# Display.net
KiCad netlist of a schematic drawn in Altium Designer
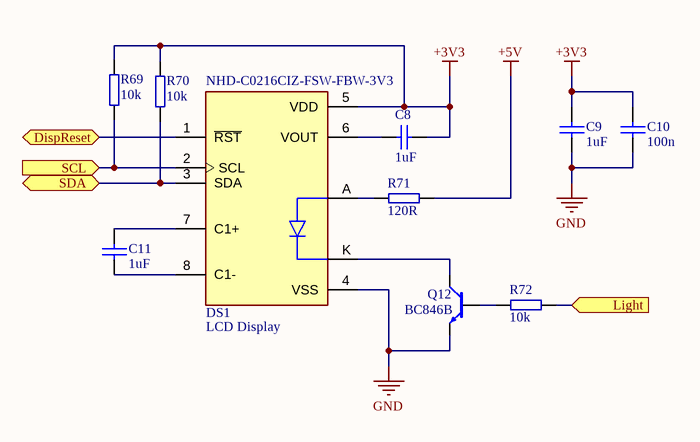
[diagram p0: Display.SchDoc]

(export (version "E")
  (design (tool "Eeschema 10.0.6"))
  (components
    (comp (ref "C8")
      (value "1uF_35V")
      (footprint "C_0603")
      (description "Capacitor [SMD]")
      (fields
        (field (name "NAME") "1uF")
        (field (name "TOLERANCE") "10%")
        (field (name "MANUFACTURER") "Murata")
      )
      (libsource (lib "PassiveBMS_schlib") (part "C_1uF_0603"))
    )
    (comp (ref "C9")
      (value "1uF_35V")
      (footprint "C_0805")
      (description "Capacitor [SMD]")
      (fields
        (field (name "NAME") "1uF")
        (field (name "TOLERANCE") "10%")
        (field (name "MANUFACTURER") "Murata")
      )
      (libsource (lib "PassiveBMS_schlib") (part "C_1uF_0805"))
    )
    (comp (ref "C10")
      (value "100nF_35V")
      (footprint "C_0805")
      (description "Capacitor [SMD]")
      (fields
        (field (name "NAME") "100n")
        (field (name "TOLERANCE") "10%")
        (field (name "MANUFACTURER") "Murata")
      )
      (libsource (lib "PassiveBMS_schlib") (part "C_100nF_0805"))
    )
    (comp (ref "C11")
      (value "1uF_35V")
      (footprint "C_0603")
      (description "Capacitor [SMD]")
      (fields
        (field (name "NAME") "1uF")
        (field (name "TOLERANCE") "10%")
        (field (name "MANUFACTURER") "Murata")
      )
      (libsource (lib "PassiveBMS_schlib") (part "C_1uF_0603"))
    )
    (comp (ref "DS1")
      (value "LCD_FSTN_Display")
      (footprint "MK_BMS_pcblib:LCD_NHD-C0216CIZ-FSW-FBW-3V3")
      (description "NHD-C0216CIZ-FSW-FBW-3V3\r\nLCD Display")
      (fields
        (field (name "MF") "Newhaven")
        (field (name "DIGI-KEY_PART_NUMBER") "NHD-C0216CIZ-FSW-FBW-3V3-ND")
        (field (name "MP") "NHD-C0216CIZ-FSW-FBW-3V3")
        (field (name "NAME") "LCD Display")
      )
      (libsource (lib "PassiveBMS_schlib") (part "LCD_FSTN_Display"))
    )
    (comp (ref "Q12")
      (value "BC846B_SOT23")
      (footprint "NPN_BJT_SOT23")
      (description "NPN transistor [SMD]")
      (fields
        (field (name "NAME") "BC846B")
        (field (name "MANUFACTURER PART NUMBER") "BC846ALT1G")
        (field (name "MANUFACTURER") "ON Semiconductor")
      )
      (libsource (lib "PassiveBMS_schlib") (part "BC846B_SOT23"))
    )
    (comp (ref "R69")
      (value "10k_125mW")
      (footprint "R_0805")
      (description "Resistor [SMD]")
      (fields
        (field (name "NAME") "10k")
        (field (name "TOLERANCE") "1%")
        (field (name "MANUFACTURER") "Vishay")
      )
      (libsource (lib "PassiveBMS_schlib") (part "R_10k_0805"))
    )
    (comp (ref "R70")
      (value "10k_125mW")
      (footprint "R_0805")
      (description "Resistor [SMD]")
      (fields
        (field (name "NAME") "10k")
        (field (name "TOLERANCE") "1%")
        (field (name "MANUFACTURER") "Vishay")
      )
      (libsource (lib "PassiveBMS_schlib") (part "R_10k_0805"))
    )
    (comp (ref "R71")
      (value "120R_125mW")
      (footprint "R_0805")
      (description "Resistor [SMD]")
      (fields
        (field (name "NAME") "120R")
        (field (name "TOLERANCE") "1%")
        (field (name "MANUFACTURER") "Vishay")
      )
      (libsource (lib "PassiveBMS_schlib") (part "R_120R_0805"))
    )
    (comp (ref "R72")
      (value "10k_125mW")
      (footprint "R_0805")
      (description "Resistor [SMD]")
      (fields
        (field (name "NAME") "10k")
        (field (name "TOLERANCE") "1%")
        (field (name "MANUFACTURER") "Vishay")
      )
      (libsource (lib "PassiveBMS_schlib") (part "R_10k_0805"))
    )
  )
  (nets
    (net (code "1") (name "+3V3") (class "Default")
      (node (ref "C10") (pin "2") (pinfunction "2_2") (pintype "passive"))
      (node (ref "C8") (pin "2") (pinfunction "2_2") (pintype "passive"))
      (node (ref "C9") (pin "2") (pinfunction "2_2") (pintype "passive"))
      (node (ref "DS1") (pin "5") (pinfunction "VDD_5") (pintype "power_in"))
      (node (ref "R69") (pin "1") (pinfunction "1_1") (pintype "passive"))
      (node (ref "R70") (pin "1") (pinfunction "1_1") (pintype "passive"))
    )
    (net (code "2") (name "+5V") (class "Default")
      (node (ref "R71") (pin "1") (pinfunction "1_1") (pintype "passive"))
    )
    (net (code "3") (name "/DispReset") (class "Default")
      (node (ref "DS1") (pin "1") (pinfunction "~{RST}_1") (pintype "passive"))
    )
    (net (code "4") (name "/Light") (class "Default")
      (node (ref "R72") (pin "1") (pinfunction "1_1") (pintype "passive"))
    )
    (net (code "5") (name "/SCL") (class "Default")
      (node (ref "DS1") (pin "2") (pinfunction "SCL_2") (pintype "passive"))
      (node (ref "R69") (pin "2") (pinfunction "2_2") (pintype "passive"))
    )
    (net (code "6") (name "/SDA") (class "Default")
      (node (ref "DS1") (pin "3") (pinfunction "SDA_3") (pintype "passive"))
      (node (ref "R70") (pin "2") (pinfunction "2_2") (pintype "passive"))
    )
    (net (code "7") (name "GND") (class "Default")
      (node (ref "C10") (pin "1") (pinfunction "1_1") (pintype "passive"))
      (node (ref "C9") (pin "1") (pinfunction "1_1") (pintype "passive"))
      (node (ref "DS1") (pin "4") (pinfunction "VSS_4") (pintype "power_in"))
      (node (ref "Q12") (pin "3") (pinfunction "E_3") (pintype "passive"))
    )
    (net (code "8") (name "Net-(DS1-C1+)") (class "Default")
      (node (ref "C11") (pin "2") (pinfunction "2_2") (pintype "passive"))
      (node (ref "DS1") (pin "7") (pinfunction "C1+_7") (pintype "passive"))
    )
    (net (code "9") (name "Net-(DS1-C1-)") (class "Default")
      (node (ref "C11") (pin "1") (pinfunction "1_1") (pintype "passive"))
      (node (ref "DS1") (pin "8") (pinfunction "C1-_8") (pintype "passive"))
    )
    (net (code "10") (name "Net-(DS1-PadA)") (class "Default")
      (node (ref "DS1") (pin "A") (pinfunction "A_A") (pintype "passive"))
      (node (ref "R71") (pin "2") (pinfunction "2_2") (pintype "passive"))
    )
    (net (code "11") (name "Net-(DS1-VOUT)") (class "Default")
      (node (ref "C8") (pin "1") (pinfunction "1_1") (pintype "passive"))
      (node (ref "DS1") (pin "6") (pinfunction "VOUT_6") (pintype "passive"))
    )
    (net (code "12") (name "Net-(Q12-B)") (class "Default")
      (node (ref "Q12") (pin "2") (pinfunction "B_2") (pintype "passive"))
      (node (ref "R72") (pin "2") (pinfunction "2_2") (pintype "passive"))
    )
    (net (code "13") (name "Net-(Q12-C)") (class "Default")
      (node (ref "DS1") (pin "K") (pinfunction "K_K") (pintype "passive"))
      (node (ref "Q12") (pin "1") (pinfunction "C_1") (pintype "passive"))
    )
  )
)
